# joystick_controller.net
KiCad netlist of a schematic drawn in EAGLE
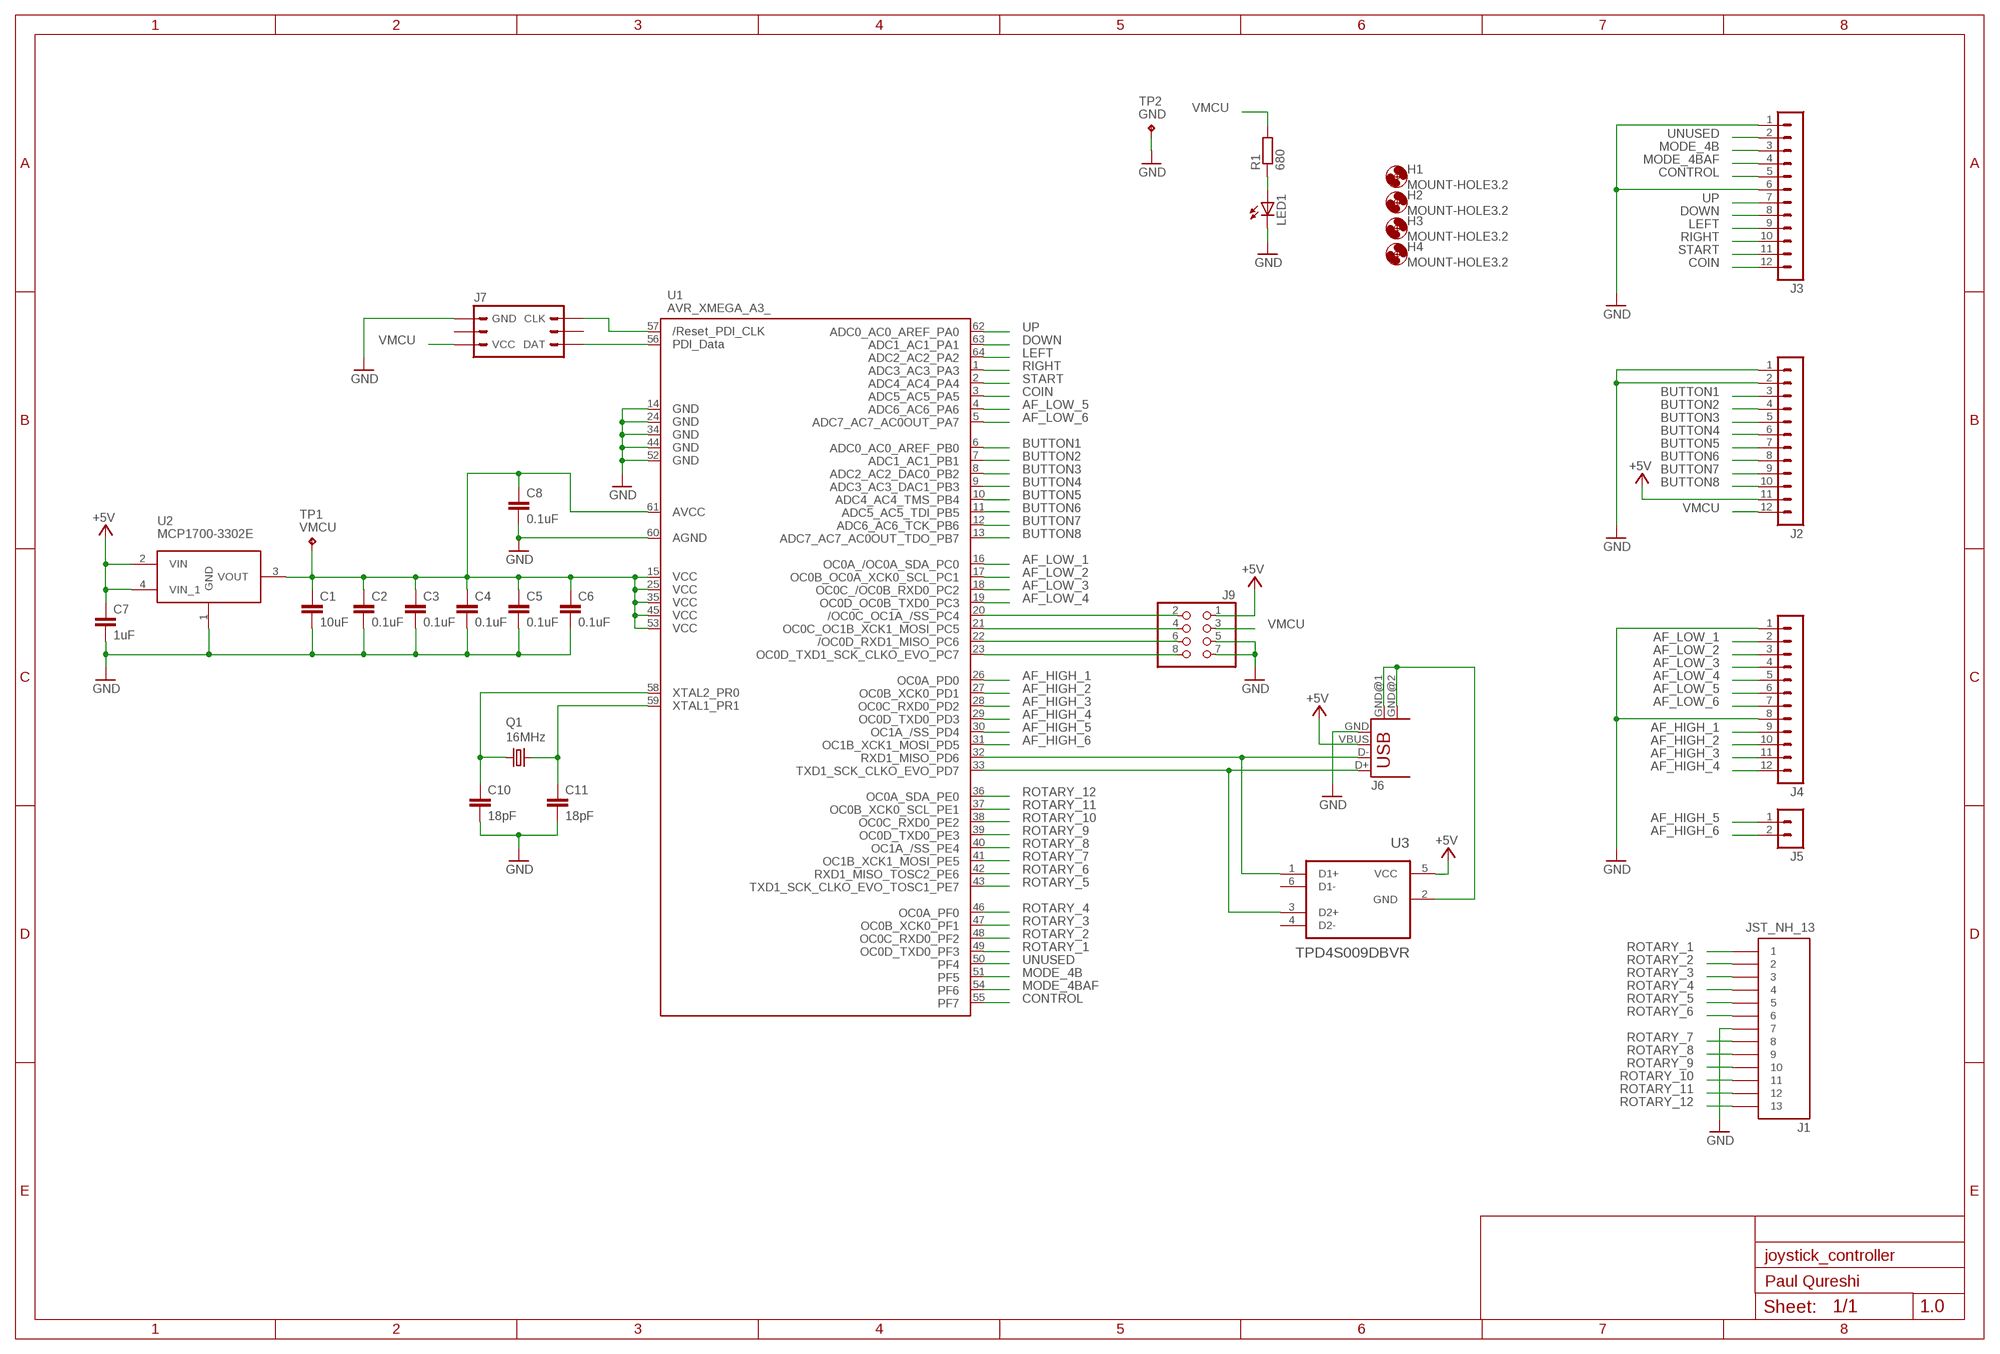
[diagram p0: schematic, sheet 1]

(export (version "E")
  (design (tool "Eeschema 10.0.6"))
  (components
    (comp (ref "C1")
      (value "10uF")
      (footprint "eagle-import:C0805")
      (libsource (lib "eagle-import") (part "C-EUC0805"))
    )
    (comp (ref "C2")
      (value "0.1uF")
      (footprint "eagle-import:C0805")
      (libsource (lib "eagle-import") (part "C-EUC0805"))
    )
    (comp (ref "C3")
      (value "0.1uF")
      (footprint "eagle-import:C0805")
      (libsource (lib "eagle-import") (part "C-EUC0805"))
    )
    (comp (ref "C4")
      (value "0.1uF")
      (footprint "eagle-import:C0805")
      (libsource (lib "eagle-import") (part "C-EUC0805"))
    )
    (comp (ref "C5")
      (value "0.1uF")
      (footprint "eagle-import:C0805")
      (libsource (lib "eagle-import") (part "C-EUC0805"))
    )
    (comp (ref "C6")
      (value "0.1uF")
      (footprint "eagle-import:C0805")
      (libsource (lib "eagle-import") (part "C-EUC0805"))
    )
    (comp (ref "C7")
      (value "1uF")
      (footprint "eagle-import:C0805")
      (libsource (lib "eagle-import") (part "C-EUC0805"))
    )
    (comp (ref "C8")
      (value "0.1uF")
      (footprint "eagle-import:C0805")
      (libsource (lib "eagle-import") (part "C-EUC0805"))
    )
    (comp (ref "C10")
      (value "18pF")
      (footprint "eagle-import:C0805")
      (libsource (lib "eagle-import") (part "C-EUC0805"))
    )
    (comp (ref "C11")
      (value "18pF")
      (footprint "eagle-import:C0805")
      (libsource (lib "eagle-import") (part "C-EUC0805"))
    )
    (comp (ref "H1")
      (value "MOUNT-HOLE3.2")
      (footprint "eagle-import:3,2")
      (libsource (lib "eagle-import") (part "MOUNT-HOLE3.2"))
    )
    (comp (ref "H2")
      (value "MOUNT-HOLE3.2")
      (footprint "eagle-import:3,2")
      (libsource (lib "eagle-import") (part "MOUNT-HOLE3.2"))
    )
    (comp (ref "H3")
      (value "MOUNT-HOLE3.2")
      (footprint "eagle-import:3,2")
      (libsource (lib "eagle-import") (part "MOUNT-HOLE3.2"))
    )
    (comp (ref "H4")
      (value "MOUNT-HOLE3.2")
      (footprint "eagle-import:3,2")
      (libsource (lib "eagle-import") (part "MOUNT-HOLE3.2"))
    )
    (comp (ref "J1")
      (value "JST_NH_13")
      (footprint "eagle-import:JST_NH_13_RA")
      (libsource (lib "eagle-import") (part "JST_NH_13"))
    )
    (comp (ref "J2")
      (value "CON-3.5TERM-12")
      (footprint "eagle-import:CON-3.5TERM-12")
      (libsource (lib "eagle-import") (part "CON-3.5TERM-12"))
    )
    (comp (ref "J3")
      (value "CON-3.5TERM-12")
      (footprint "eagle-import:CON-3.5TERM-12")
      (libsource (lib "eagle-import") (part "CON-3.5TERM-12"))
    )
    (comp (ref "J4")
      (value "CON-3.5TERM-12")
      (footprint "eagle-import:CON-3.5TERM-12")
      (libsource (lib "eagle-import") (part "CON-3.5TERM-12"))
    )
    (comp (ref "J5")
      (value "CON-3.5TERM-2")
      (footprint "eagle-import:CON-3.5TERM-2")
      (libsource (lib "eagle-import") (part "CON-3.5TERM-2"))
    )
    (comp (ref "J6")
      (value "USB-B-H")
      (footprint "eagle-import:USB-B-H")
      (libsource (lib "eagle-import") (part "USB-B-H"))
    )
    (comp (ref "J7")
      (value "PDI_HEADER")
      (footprint "eagle-import:MA03-2")
      (libsource (lib "eagle-import") (part "PDI_HEADER"))
    )
    (comp (ref "J9")
      (value "PINHD-2X4")
      (footprint "eagle-import:2X04")
      (libsource (lib "eagle-import") (part "PINHD-2X4"))
    )
    (comp (ref "LED1")
      (value "LEDCHIP-LED0805")
      (footprint "eagle-import:CHIP-LED0805")
      (libsource (lib "eagle-import") (part "LEDCHIP-LED0805"))
    )
    (comp (ref "Q1")
      (value "16MHz")
      (footprint "eagle-import:HC49_S")
      (libsource (lib "eagle-import") (part "CRYSTALHC49S"))
    )
    (comp (ref "R1")
      (value "680")
      (footprint "eagle-import:R0805")
      (libsource (lib "eagle-import") (part "R-EU_R0805"))
    )
    (comp (ref "TP1")
      (value "VMCU")
      (footprint "eagle-import:HARWIN-S1751-46")
      (libsource (lib "eagle-import") (part "TEST_POINTS1751"))
    )
    (comp (ref "TP2")
      (value "GND")
      (footprint "eagle-import:HARWIN-S1751-46")
      (libsource (lib "eagle-import") (part "TEST_POINTS1751"))
    )
    (comp (ref "U1")
      (value "AVR_XMEGA_A3_")
      (footprint "eagle-import:TQFP64")
      (libsource (lib "eagle-import") (part "AVR_XMEGA_A3_"))
    )
    (comp (ref "U2")
      (value "MCP1700-3302E")
      (footprint "eagle-import:SOT150P400X160-4N")
      (fields (field (name "MPN") "MCP1700T-3302E/MB"))
      (libsource (lib "eagle-import") (part "MCP17-MCP1700T-3302E/MB"))
    )
    (comp (ref "U3")
      (value "TPD4S009DBVR")
      (footprint "eagle-import:SOT95P280X145-6N")
      (libsource (lib "eagle-import") (part "TPD4S009DBVR"))
    )
  )
  (nets
    (net (code "1") (name "+5V") (class "Default")
      (node (ref "C7") (pin "1") (pinfunction "1_1") (pintype "passive"))
      (node (ref "J2") (pin "11") (pinfunction "11_11") (pintype "passive"))
      (node (ref "J6") (pin "VBUS") (pinfunction "VBUS_VBUS") (pintype "bidirectional"))
      (node (ref "J9") (pin "1") (pinfunction "1_1") (pintype "passive"))
      (node (ref "U2") (pin "2") (pinfunction "VIN_2") (pintype "input"))
      (node (ref "U2") (pin "4") (pinfunction "VIN_1_4") (pintype "input"))
      (node (ref "U3") (pin "5") (pinfunction "VCC_5") (pintype "power_in"))
    )
    (net (code "2") (name "/AF_HIGH_1") (class "Default")
      (node (ref "J4") (pin "9") (pinfunction "9_9") (pintype "passive"))
      (node (ref "U1") (pin "26") (pinfunction "PD0_26") (pintype "bidirectional"))
    )
    (net (code "3") (name "/AF_HIGH_2") (class "Default")
      (node (ref "J4") (pin "10") (pinfunction "10_10") (pintype "passive"))
      (node (ref "U1") (pin "27") (pinfunction "PD1_27") (pintype "bidirectional"))
    )
    (net (code "4") (name "/AF_HIGH_3") (class "Default")
      (node (ref "J4") (pin "11") (pinfunction "11_11") (pintype "passive"))
      (node (ref "U1") (pin "28") (pinfunction "PD2_28") (pintype "bidirectional"))
    )
    (net (code "5") (name "/AF_HIGH_4") (class "Default")
      (node (ref "J4") (pin "12") (pinfunction "12_12") (pintype "passive"))
      (node (ref "U1") (pin "29") (pinfunction "PD3_29") (pintype "bidirectional"))
    )
    (net (code "6") (name "/AF_HIGH_5") (class "Default")
      (node (ref "J5") (pin "1") (pinfunction "1_1") (pintype "passive"))
      (node (ref "U1") (pin "30") (pinfunction "PD4_30") (pintype "bidirectional"))
    )
    (net (code "7") (name "/AF_HIGH_6") (class "Default")
      (node (ref "J5") (pin "2") (pinfunction "2_2") (pintype "passive"))
      (node (ref "U1") (pin "31") (pinfunction "PD5_31") (pintype "bidirectional"))
    )
    (net (code "8") (name "/AF_LOW_1") (class "Default")
      (node (ref "J4") (pin "2") (pinfunction "2_2") (pintype "passive"))
      (node (ref "U1") (pin "16") (pinfunction "PC0_16") (pintype "bidirectional"))
    )
    (net (code "9") (name "/AF_LOW_2") (class "Default")
      (node (ref "J4") (pin "3") (pinfunction "3_3") (pintype "passive"))
      (node (ref "U1") (pin "17") (pinfunction "PC1_17") (pintype "bidirectional"))
    )
    (net (code "10") (name "/AF_LOW_3") (class "Default")
      (node (ref "J4") (pin "4") (pinfunction "4_4") (pintype "passive"))
      (node (ref "U1") (pin "18") (pinfunction "PC2_18") (pintype "bidirectional"))
    )
    (net (code "11") (name "/AF_LOW_4") (class "Default")
      (node (ref "J4") (pin "5") (pinfunction "5_5") (pintype "passive"))
      (node (ref "U1") (pin "19") (pinfunction "PC3_19") (pintype "bidirectional"))
    )
    (net (code "12") (name "/AF_LOW_5") (class "Default")
      (node (ref "J4") (pin "6") (pinfunction "6_6") (pintype "passive"))
      (node (ref "U1") (pin "4") (pinfunction "PA6_4") (pintype "bidirectional"))
    )
    (net (code "13") (name "/AF_LOW_6") (class "Default")
      (node (ref "J4") (pin "7") (pinfunction "7_7") (pintype "passive"))
      (node (ref "U1") (pin "5") (pinfunction "PA7_5") (pintype "bidirectional"))
    )
    (net (code "14") (name "/BUTTON1") (class "Default")
      (node (ref "J2") (pin "3") (pinfunction "3_3") (pintype "passive"))
      (node (ref "U1") (pin "6") (pinfunction "PB0_6") (pintype "bidirectional"))
    )
    (net (code "15") (name "/BUTTON2") (class "Default")
      (node (ref "J2") (pin "4") (pinfunction "4_4") (pintype "passive"))
      (node (ref "U1") (pin "7") (pinfunction "PB1_7") (pintype "bidirectional"))
    )
    (net (code "16") (name "/BUTTON3") (class "Default")
      (node (ref "J2") (pin "5") (pinfunction "5_5") (pintype "passive"))
      (node (ref "U1") (pin "8") (pinfunction "PB2_8") (pintype "bidirectional"))
    )
    (net (code "17") (name "/BUTTON4") (class "Default")
      (node (ref "J2") (pin "6") (pinfunction "6_6") (pintype "passive"))
      (node (ref "U1") (pin "9") (pinfunction "PB3_9") (pintype "bidirectional"))
    )
    (net (code "18") (name "/BUTTON5") (class "Default")
      (node (ref "J2") (pin "7") (pinfunction "7_7") (pintype "passive"))
      (node (ref "U1") (pin "10") (pinfunction "PB4_10") (pintype "bidirectional"))
    )
    (net (code "19") (name "/BUTTON6") (class "Default")
      (node (ref "J2") (pin "8") (pinfunction "8_8") (pintype "passive"))
      (node (ref "U1") (pin "11") (pinfunction "PB5_11") (pintype "bidirectional"))
    )
    (net (code "20") (name "/BUTTON7") (class "Default")
      (node (ref "J2") (pin "9") (pinfunction "9_9") (pintype "passive"))
      (node (ref "U1") (pin "12") (pinfunction "PB6_12") (pintype "bidirectional"))
    )
    (net (code "21") (name "/BUTTON8") (class "Default")
      (node (ref "J2") (pin "10") (pinfunction "10_10") (pintype "passive"))
      (node (ref "U1") (pin "13") (pinfunction "PB7_13") (pintype "bidirectional"))
    )
    (net (code "22") (name "/COIN") (class "Default")
      (node (ref "J3") (pin "12") (pinfunction "12_12") (pintype "passive"))
      (node (ref "U1") (pin "3") (pinfunction "PA5_3") (pintype "bidirectional"))
    )
    (net (code "23") (name "/CONTROL") (class "Default")
      (node (ref "J3") (pin "5") (pinfunction "5_5") (pintype "passive"))
      (node (ref "U1") (pin "55") (pinfunction "PF7_55") (pintype "bidirectional"))
    )
    (net (code "24") (name "/DOWN") (class "Default")
      (node (ref "J3") (pin "8") (pinfunction "8_8") (pintype "passive"))
      (node (ref "U1") (pin "63") (pinfunction "PA1_63") (pintype "bidirectional"))
    )
    (net (code "25") (name "/LEFT") (class "Default")
      (node (ref "J3") (pin "9") (pinfunction "9_9") (pintype "passive"))
      (node (ref "U1") (pin "64") (pinfunction "PA2_64") (pintype "bidirectional"))
    )
    (net (code "26") (name "/MODE_4B") (class "Default")
      (node (ref "J3") (pin "3") (pinfunction "3_3") (pintype "passive"))
      (node (ref "U1") (pin "51") (pinfunction "PF5_51") (pintype "bidirectional"))
    )
    (net (code "27") (name "/MODE_4BAF") (class "Default")
      (node (ref "J3") (pin "4") (pinfunction "4_4") (pintype "passive"))
      (node (ref "U1") (pin "54") (pinfunction "PF6_54") (pintype "bidirectional"))
    )
    (net (code "28") (name "/RIGHT") (class "Default")
      (node (ref "J3") (pin "10") (pinfunction "10_10") (pintype "passive"))
      (node (ref "U1") (pin "1") (pinfunction "PA3_1") (pintype "bidirectional"))
    )
    (net (code "29") (name "/ROTARY_1") (class "Default")
      (node (ref "J1") (pin "1") (pinfunction "1_1") (pintype "passive"))
      (node (ref "U1") (pin "49") (pinfunction "PF3_49") (pintype "bidirectional"))
    )
    (net (code "30") (name "/ROTARY_2") (class "Default")
      (node (ref "J1") (pin "2") (pinfunction "2_2") (pintype "passive"))
      (node (ref "U1") (pin "48") (pinfunction "PF2_48") (pintype "bidirectional"))
    )
    (net (code "31") (name "/ROTARY_3") (class "Default")
      (node (ref "J1") (pin "3") (pinfunction "3_3") (pintype "passive"))
      (node (ref "U1") (pin "47") (pinfunction "PF1_47") (pintype "bidirectional"))
    )
    (net (code "32") (name "/ROTARY_4") (class "Default")
      (node (ref "J1") (pin "4") (pinfunction "4_4") (pintype "passive"))
      (node (ref "U1") (pin "46") (pinfunction "PF0_46") (pintype "bidirectional"))
    )
    (net (code "33") (name "/ROTARY_5") (class "Default")
      (node (ref "J1") (pin "5") (pinfunction "5_5") (pintype "passive"))
      (node (ref "U1") (pin "43") (pinfunction "PE7_43") (pintype "bidirectional"))
    )
    (net (code "34") (name "/ROTARY_6") (class "Default")
      (node (ref "J1") (pin "6") (pinfunction "6_6") (pintype "passive"))
      (node (ref "U1") (pin "42") (pinfunction "PE6_42") (pintype "bidirectional"))
    )
    (net (code "35") (name "/ROTARY_7") (class "Default")
      (node (ref "J1") (pin "8") (pinfunction "8_8") (pintype "passive"))
      (node (ref "U1") (pin "41") (pinfunction "PE5_41") (pintype "bidirectional"))
    )
    (net (code "36") (name "/ROTARY_8") (class "Default")
      (node (ref "J1") (pin "9") (pinfunction "9_9") (pintype "passive"))
      (node (ref "U1") (pin "40") (pinfunction "PE4_40") (pintype "bidirectional"))
    )
    (net (code "37") (name "/ROTARY_9") (class "Default")
      (node (ref "J1") (pin "10") (pinfunction "10_10") (pintype "passive"))
      (node (ref "U1") (pin "39") (pinfunction "PE3_39") (pintype "bidirectional"))
    )
    (net (code "38") (name "/ROTARY_10") (class "Default")
      (node (ref "J1") (pin "11") (pinfunction "11_11") (pintype "passive"))
      (node (ref "U1") (pin "38") (pinfunction "PE2_38") (pintype "bidirectional"))
    )
    (net (code "39") (name "/ROTARY_11") (class "Default")
      (node (ref "J1") (pin "12") (pinfunction "12_12") (pintype "passive"))
      (node (ref "U1") (pin "37") (pinfunction "PE1_37") (pintype "bidirectional"))
    )
    (net (code "40") (name "/ROTARY_12") (class "Default")
      (node (ref "J1") (pin "13") (pinfunction "13_13") (pintype "passive"))
      (node (ref "U1") (pin "36") (pinfunction "PE0_36") (pintype "bidirectional"))
    )
    (net (code "41") (name "/START") (class "Default")
      (node (ref "J3") (pin "11") (pinfunction "11_11") (pintype "passive"))
      (node (ref "U1") (pin "2") (pinfunction "PA4_2") (pintype "bidirectional"))
    )
    (net (code "42") (name "/UNUSED") (class "Default")
      (node (ref "J3") (pin "2") (pinfunction "2_2") (pintype "passive"))
      (node (ref "U1") (pin "50") (pinfunction "PF4_50") (pintype "bidirectional"))
    )
    (net (code "43") (name "/UP") (class "Default")
      (node (ref "J3") (pin "7") (pinfunction "7_7") (pintype "passive"))
      (node (ref "U1") (pin "62") (pinfunction "PA0_62") (pintype "bidirectional"))
    )
    (net (code "44") (name "/VMCU") (class "Default")
      (node (ref "C1") (pin "1") (pinfunction "1_1") (pintype "passive"))
      (node (ref "C2") (pin "1") (pinfunction "1_1") (pintype "passive"))
      (node (ref "C3") (pin "1") (pinfunction "1_1") (pintype "passive"))
      (node (ref "C4") (pin "1") (pinfunction "1_1") (pintype "passive"))
      (node (ref "C5") (pin "1") (pinfunction "1_1") (pintype "passive"))
      (node (ref "C6") (pin "1") (pinfunction "1_1") (pintype "passive"))
      (node (ref "C8") (pin "1") (pinfunction "1_1") (pintype "passive"))
      (node (ref "J2") (pin "12") (pinfunction "12_12") (pintype "passive"))
      (node (ref "J7") (pin "2") (pinfunction "VCC_2") (pintype "passive"))
      (node (ref "J9") (pin "3") (pinfunction "3_3") (pintype "passive"))
      (node (ref "R1") (pin "2") (pinfunction "2_2") (pintype "passive"))
      (node (ref "TP1") (pin "P$1") (pinfunction "Q1_P$1") (pintype "passive"))
      (node (ref "U1") (pin "15") (pinfunction "VCC1_15") (pintype "bidirectional"))
      (node (ref "U1") (pin "25") (pinfunction "VCC2_25") (pintype "bidirectional"))
      (node (ref "U1") (pin "35") (pinfunction "VCC3_35") (pintype "bidirectional"))
      (node (ref "U1") (pin "45") (pinfunction "VCC4_45") (pintype "bidirectional"))
      (node (ref "U1") (pin "53") (pinfunction "VCC5_53") (pintype "bidirectional"))
      (node (ref "U1") (pin "61") (pinfunction "AVCC_61") (pintype "bidirectional"))
      (node (ref "U2") (pin "3") (pinfunction "VOUT_3") (pintype "output"))
    )
    (net (code "45") (name "GND") (class "Default")
      (node (ref "C1") (pin "2") (pinfunction "2_2") (pintype "passive"))
      (node (ref "C10") (pin "2") (pinfunction "2_2") (pintype "passive"))
      (node (ref "C11") (pin "2") (pinfunction "2_2") (pintype "passive"))
      (node (ref "C2") (pin "2") (pinfunction "2_2") (pintype "passive"))
      (node (ref "C3") (pin "2") (pinfunction "2_2") (pintype "passive"))
      (node (ref "C4") (pin "2") (pinfunction "2_2") (pintype "passive"))
      (node (ref "C5") (pin "2") (pinfunction "2_2") (pintype "passive"))
      (node (ref "C6") (pin "2") (pinfunction "2_2") (pintype "passive"))
      (node (ref "C7") (pin "2") (pinfunction "2_2") (pintype "passive"))
      (node (ref "C8") (pin "2") (pinfunction "2_2") (pintype "passive"))
      (node (ref "J1") (pin "7") (pinfunction "7_7") (pintype "passive"))
      (node (ref "J2") (pin "1") (pinfunction "1_1") (pintype "passive"))
      (node (ref "J2") (pin "2") (pinfunction "2_2") (pintype "passive"))
      (node (ref "J3") (pin "1") (pinfunction "1_1") (pintype "passive"))
      (node (ref "J3") (pin "6") (pinfunction "6_6") (pintype "passive"))
      (node (ref "J4") (pin "1") (pinfunction "1_1") (pintype "passive"))
      (node (ref "J4") (pin "8") (pinfunction "8_8") (pintype "passive"))
      (node (ref "J6") (pin "GND") (pinfunction "GND_GND") (pintype "bidirectional"))
      (node (ref "J7") (pin "6") (pinfunction "GND_6") (pintype "passive"))
      (node (ref "J9") (pin "5") (pinfunction "5_5") (pintype "passive"))
      (node (ref "J9") (pin "7") (pinfunction "7_7") (pintype "passive"))
      (node (ref "LED1") (pin "C") (pinfunction "C_C") (pintype "passive"))
      (node (ref "TP2") (pin "P$1") (pinfunction "Q1_P$1") (pintype "passive"))
      (node (ref "U1") (pin "14") (pinfunction "GND1_14") (pintype "bidirectional"))
      (node (ref "U1") (pin "24") (pinfunction "GND2_24") (pintype "bidirectional"))
      (node (ref "U1") (pin "34") (pinfunction "GND3_34") (pintype "bidirectional"))
      (node (ref "U1") (pin "44") (pinfunction "GND4_44") (pintype "bidirectional"))
      (node (ref "U1") (pin "52") (pinfunction "GND5_52") (pintype "bidirectional"))
      (node (ref "U1") (pin "60") (pinfunction "AGND_60") (pintype "bidirectional"))
      (node (ref "U2") (pin "1") (pinfunction "GND_1") (pintype "power_in"))
    )
    (net (code "46") (name "Net-(J7-CLK)") (class "Default")
      (node (ref "J7") (pin "5") (pinfunction "CLK_5") (pintype "passive"))
      (node (ref "U1") (pin "57") (pinfunction "RESET_57") (pintype "bidirectional"))
    )
    (net (code "47") (name "Net-(J7-DAT)") (class "Default")
      (node (ref "J7") (pin "1") (pinfunction "DAT_1") (pintype "passive"))
      (node (ref "U1") (pin "56") (pinfunction "PDI_DATA_56") (pintype "bidirectional"))
    )
    (net (code "48") (name "Net-(LED1-PadA)") (class "Default")
      (node (ref "LED1") (pin "A") (pinfunction "A_A") (pintype "passive"))
      (node (ref "R1") (pin "1") (pinfunction "1_1") (pintype "passive"))
    )
    (net (code "49") (name "Net-(U1-PC4)") (class "Default")
      (node (ref "J9") (pin "2") (pinfunction "2_2") (pintype "passive"))
      (node (ref "U1") (pin "20") (pinfunction "PC4_20") (pintype "bidirectional"))
    )
    (net (code "50") (name "Net-(U1-PC5)") (class "Default")
      (node (ref "J9") (pin "4") (pinfunction "4_4") (pintype "passive"))
      (node (ref "U1") (pin "21") (pinfunction "PC5_21") (pintype "bidirectional"))
    )
    (net (code "51") (name "Net-(U1-PC6)") (class "Default")
      (node (ref "J9") (pin "6") (pinfunction "6_6") (pintype "passive"))
      (node (ref "U1") (pin "22") (pinfunction "PC6_22") (pintype "bidirectional"))
    )
    (net (code "52") (name "Net-(U1-PC7)") (class "Default")
      (node (ref "J9") (pin "8") (pinfunction "8_8") (pintype "passive"))
      (node (ref "U1") (pin "23") (pinfunction "PC7_23") (pintype "bidirectional"))
    )
    (net (code "53") (name "Net-(U1-PD6)") (class "Default")
      (node (ref "J6") (pin "D-") (pinfunction "D-_D-") (pintype "bidirectional"))
      (node (ref "U1") (pin "32") (pinfunction "PD6_32") (pintype "bidirectional"))
      (node (ref "U3") (pin "1") (pinfunction "D1+_1") (pintype "input"))
    )
    (net (code "54") (name "Net-(U1-PD7)") (class "Default")
      (node (ref "J6") (pin "D+") (pinfunction "D+_D+") (pintype "bidirectional"))
      (node (ref "U1") (pin "33") (pinfunction "PD7_33") (pintype "bidirectional"))
      (node (ref "U3") (pin "3") (pinfunction "D2+_3") (pintype "input"))
    )
    (net (code "55") (name "Net-(U1-PR0)") (class "Default")
      (node (ref "C10") (pin "1") (pinfunction "1_1") (pintype "passive"))
      (node (ref "Q1") (pin "1") (pinfunction "1_1") (pintype "passive"))
      (node (ref "U1") (pin "58") (pinfunction "PR0_58") (pintype "bidirectional"))
    )
    (net (code "56") (name "Net-(U1-PR1)") (class "Default")
      (node (ref "C11") (pin "1") (pinfunction "1_1") (pintype "passive"))
      (node (ref "Q1") (pin "2") (pinfunction "2_2") (pintype "passive"))
      (node (ref "U1") (pin "59") (pinfunction "PR1_59") (pintype "bidirectional"))
    )
    (net (code "57") (name "Net-(U3-GND)") (class "Default")
      (node (ref "J6") (pin "GND@1") (pinfunction "GND_GND@1") (pintype "bidirectional"))
      (node (ref "J6") (pin "GND@2") (pinfunction "GND_GND@2") (pintype "bidirectional"))
      (node (ref "U3") (pin "2") (pinfunction "GND_2") (pintype "passive"))
    )
    (net (code "58") (name "unconnected-(J7-NC-Pad3)") (class "Default")
      (node (ref "J7") (pin "3") (pinfunction "NC_3") (pintype "passive"))
    )
    (net (code "59") (name "unconnected-(J7-NC-Pad4)") (class "Default")
      (node (ref "J7") (pin "4") (pinfunction "NC_4") (pintype "passive"))
    )
    (net (code "60") (name "unconnected-(U3-D1--Pad6)") (class "Default")
      (node (ref "U3") (pin "6") (pinfunction "D1-_6") (pintype "input"))
    )
    (net (code "61") (name "unconnected-(U3-D2--Pad4)") (class "Default")
      (node (ref "U3") (pin "4") (pinfunction "D2-_4") (pintype "input"))
    )
  )
)
